# Camera.net
KiCad netlist of a schematic drawn in Altium Designer
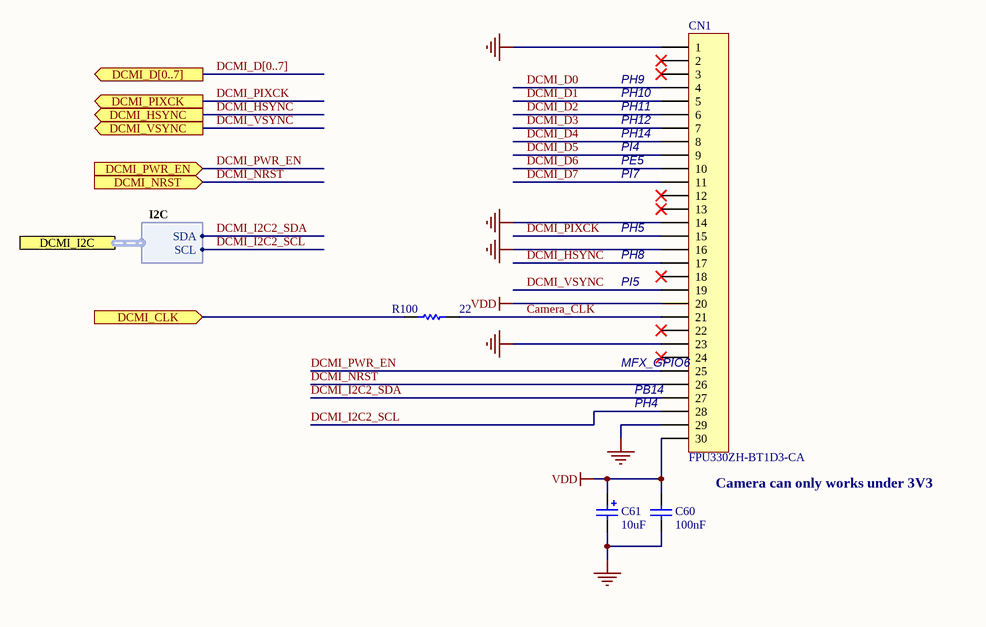
[diagram p0: Camera.SchDoc]

(export (version "E")
  (design (tool "Eeschema 10.0.6"))
  (components
    (comp (ref "C60")
      (value "100nF")
      (footprint "0603C")
      (description "Capacitor,100nF,10%,16V,X7R,0603,YAGEO")
      (fields (field (name "Comment") "CC0603KRX7R7BB104") (field (name "PUBLISHER") "Altium Limited"))
      (libsource (lib "Miscellaneous Devices") (part "Cap"))
    )
    (comp (ref "C61")
      (value "10uF")
      (footprint "TAN-A")
      (description "TAN Capacitor,10uF,10%,16V,A Type,AVX")
      (fields (field (name "Comment") "TAJA106K016R") (field (name "PUBLISHER") "Altium Limited"))
      (libsource (lib "Miscellaneous Devices") (part "Cap Pol1"))
    )
    (comp (ref "CN1")
      (value "FPU330ZH-BT1D3-CA")
      (footprint "FPU330ZH-BT1D3-CA")
      (description "TOWNES -  Connector FFC/FPC ZIF 0.5mm 30 pins, Lower Contacts")
      (libsource (lib "MCD_TOOLS") (part "FPU330ZH-BT1D3-CA"))
    )
    (comp (ref "R100")
      (value "22")
      (footprint "0603R")
      (description "Resistor, 22 ,0603,1%,YAGEO")
      (fields (field (name "Comment") "RC0603JR-0722RL") (field (name "PUBLISHER") "Altium Limited"))
      (libsource (lib "Miscellaneous Devices") (part "res1"))
    )
  )
  (nets
    (net (code "2") (name "/Camera_CLK") (class "Default")
      (node (ref "CN1") (pin "21") (pinfunction "21_21") (pintype "passive"))
      (node (ref "R100") (pin "1") (pinfunction "1_1") (pintype "passive"))
    )
    (net (code "3") (name "/DCMI_CLK") (class "Default")
      (node (ref "R100") (pin "2") (pinfunction "2_2") (pintype "passive"))
    )
    (net (code "4") (name "/DCMI_D0") (class "Default")
      (node (ref "CN1") (pin "4") (pinfunction "4_4") (pintype "passive"))
    )
    (net (code "5") (name "/DCMI_D1") (class "Default")
      (node (ref "CN1") (pin "5") (pinfunction "5_5") (pintype "passive"))
    )
    (net (code "6") (name "/DCMI_D2") (class "Default")
      (node (ref "CN1") (pin "6") (pinfunction "6_6") (pintype "passive"))
    )
    (net (code "7") (name "/DCMI_D3") (class "Default")
      (node (ref "CN1") (pin "7") (pinfunction "7_7") (pintype "passive"))
    )
    (net (code "8") (name "/DCMI_D4") (class "Default")
      (node (ref "CN1") (pin "8") (pinfunction "8_8") (pintype "passive"))
    )
    (net (code "9") (name "/DCMI_D5") (class "Default")
      (node (ref "CN1") (pin "9") (pinfunction "9_9") (pintype "passive"))
    )
    (net (code "10") (name "/DCMI_D6") (class "Default")
      (node (ref "CN1") (pin "10") (pinfunction "10_10") (pintype "passive"))
    )
    (net (code "11") (name "/DCMI_D7") (class "Default")
      (node (ref "CN1") (pin "11") (pinfunction "11_11") (pintype "passive"))
    )
    (net (code "13") (name "/DCMI_HSYNC") (class "Default")
      (node (ref "CN1") (pin "17") (pinfunction "17_17") (pintype "passive"))
    )
    (net (code "14") (name "/DCMI_I2C2_SCL") (class "Default")
      (node (ref "CN1") (pin "28") (pinfunction "28_28") (pintype "passive"))
    )
    (net (code "15") (name "/DCMI_I2C2_SDA") (class "Default")
      (node (ref "CN1") (pin "27") (pinfunction "27_27") (pintype "passive"))
    )
    (net (code "16") (name "/DCMI_NRST") (class "Default")
      (node (ref "CN1") (pin "26") (pinfunction "26_26") (pintype "passive"))
    )
    (net (code "17") (name "/DCMI_PIXCK") (class "Default")
      (node (ref "CN1") (pin "15") (pinfunction "15_15") (pintype "passive"))
    )
    (net (code "18") (name "/DCMI_PWR_EN") (class "Default")
      (node (ref "CN1") (pin "25") (pinfunction "25_25") (pintype "passive"))
    )
    (net (code "19") (name "/DCMI_VSYNC") (class "Default")
      (node (ref "CN1") (pin "19") (pinfunction "19_19") (pintype "passive"))
    )
    (net (code "21") (name "GND") (class "Default")
      (node (ref "C60") (pin "2") (pinfunction "2_2") (pintype "passive"))
      (node (ref "C61") (pin "2") (pinfunction "2_2") (pintype "passive"))
      (node (ref "CN1") (pin "1") (pinfunction "1_1") (pintype "passive"))
      (node (ref "CN1") (pin "14") (pinfunction "14_14") (pintype "passive"))
      (node (ref "CN1") (pin "16") (pinfunction "16_16") (pintype "passive"))
      (node (ref "CN1") (pin "23") (pinfunction "23_23") (pintype "passive"))
      (node (ref "CN1") (pin "29") (pinfunction "29_29") (pintype "passive"))
    )
    (net (code "22") (name "VDD") (class "Default")
      (node (ref "C60") (pin "1") (pinfunction "1_1") (pintype "passive"))
      (node (ref "C61") (pin "1") (pinfunction "1_1") (pintype "passive"))
      (node (ref "CN1") (pin "20") (pinfunction "20_20") (pintype "passive"))
      (node (ref "CN1") (pin "30") (pinfunction "30_30") (pintype "passive"))
    )
    (net (code "23") (name "unconnected-(CN1-Pad2)") (class "Default")
      (node (ref "CN1") (pin "2") (pinfunction "2_2") (pintype "passive+no_connect"))
    )
    (net (code "24") (name "unconnected-(CN1-Pad3)") (class "Default")
      (node (ref "CN1") (pin "3") (pinfunction "3_3") (pintype "passive+no_connect"))
    )
    (net (code "25") (name "unconnected-(CN1-Pad12)") (class "Default")
      (node (ref "CN1") (pin "12") (pinfunction "12_12") (pintype "passive+no_connect"))
    )
    (net (code "26") (name "unconnected-(CN1-Pad13)") (class "Default")
      (node (ref "CN1") (pin "13") (pinfunction "13_13") (pintype "passive+no_connect"))
    )
    (net (code "27") (name "unconnected-(CN1-Pad18)") (class "Default")
      (node (ref "CN1") (pin "18") (pinfunction "18_18") (pintype "passive+no_connect"))
    )
    (net (code "28") (name "unconnected-(CN1-Pad22)") (class "Default")
      (node (ref "CN1") (pin "22") (pinfunction "22_22") (pintype "passive+no_connect"))
    )
    (net (code "29") (name "unconnected-(CN1-Pad24)") (class "Default")
      (node (ref "CN1") (pin "24") (pinfunction "24_24") (pintype "passive+no_connect"))
    )
  )
)
